# Intan_32.net
KiCad netlist of a schematic drawn in EAGLE
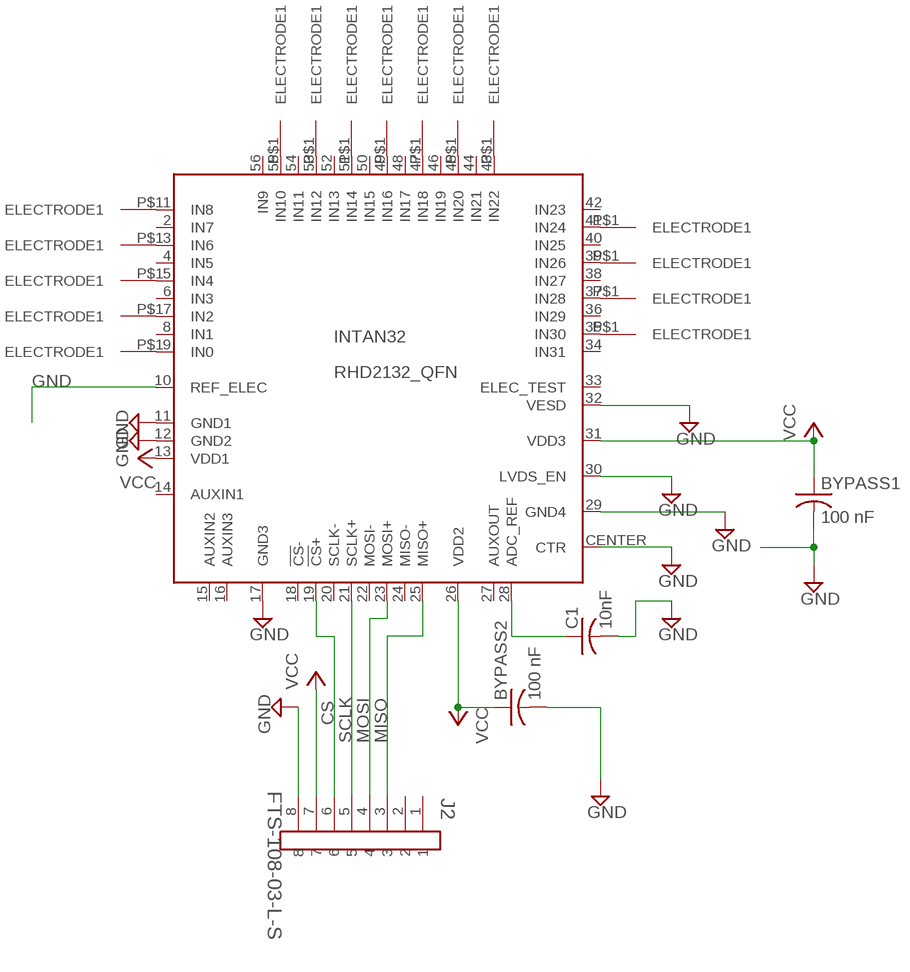
[diagram p0: schematic, sheet 1]

(export (version "E")
  (design (tool "Eeschema 10.0.6"))
  (components
    (comp (ref "BYPASS1")
      (value "100 nF")
      (footprint "eagle-import:C0402")
      (libsource (lib "eagle-import") (part "C-USC0402"))
    )
    (comp (ref "BYPASS2")
      (value "100 nF")
      (footprint "eagle-import:C0402")
      (libsource (lib "eagle-import") (part "C-USC0402"))
    )
    (comp (ref "C1")
      (value "10nF")
      (footprint "eagle-import:C0402")
      (libsource (lib "eagle-import") (part "C-USC0402"))
    )
    (comp (ref "INTAN32")
      (value "RHD2132_QFN")
      (footprint "eagle-import:QFN56_8_X_8_LARGE")
      (libsource (lib "eagle-import") (part "RHD2132_QFN"))
    )
    (comp (ref "J2")
      (value "FTS-108-03-L-S")
      (footprint "eagle-import:SAMTEC_FTS-108-03-S")
      (fields (field (name "MPN") "FTS-108-03-L-D"))
      (libsource (lib "eagle-import") (part "FTS-108-03-L-S"))
    )
    (comp (ref "U$1")
      (value "INTAN_ELECTRODE_HOLE_2323MIL")
      (footprint "eagle-import:INTAN_ELECTRODE_HOLE_23")
      (libsource (lib "eagle-import") (part "INTAN_ELECTRODE_HOLE_2323MIL"))
    )
    (comp (ref "U$2")
      (value "INTAN_ELECTRODE_HOLE_2323MIL")
      (footprint "eagle-import:INTAN_ELECTRODE_HOLE_23")
      (libsource (lib "eagle-import") (part "INTAN_ELECTRODE_HOLE_2323MIL"))
    )
    (comp (ref "U$3")
      (value "INTAN_ELECTRODE_HOLE_2323MIL")
      (footprint "eagle-import:INTAN_ELECTRODE_HOLE_23")
      (libsource (lib "eagle-import") (part "INTAN_ELECTRODE_HOLE_2323MIL"))
    )
    (comp (ref "U$4")
      (value "INTAN_ELECTRODE_HOLE_2323MIL")
      (footprint "eagle-import:INTAN_ELECTRODE_HOLE_23")
      (libsource (lib "eagle-import") (part "INTAN_ELECTRODE_HOLE_2323MIL"))
    )
    (comp (ref "U$5")
      (value "INTAN_ELECTRODE_HOLE_2323MIL")
      (footprint "eagle-import:INTAN_ELECTRODE_HOLE_23")
      (libsource (lib "eagle-import") (part "INTAN_ELECTRODE_HOLE_2323MIL"))
    )
    (comp (ref "U$6")
      (value "INTAN_ELECTRODE_HOLE_2323MIL")
      (footprint "eagle-import:INTAN_ELECTRODE_HOLE_23")
      (libsource (lib "eagle-import") (part "INTAN_ELECTRODE_HOLE_2323MIL"))
    )
    (comp (ref "U$7")
      (value "INTAN_ELECTRODE_HOLE_2323MIL")
      (footprint "eagle-import:INTAN_ELECTRODE_HOLE_23")
      (libsource (lib "eagle-import") (part "INTAN_ELECTRODE_HOLE_2323MIL"))
    )
    (comp (ref "U$8")
      (value "INTAN_ELECTRODE_HOLE_2323MIL")
      (footprint "eagle-import:INTAN_ELECTRODE_HOLE_23")
      (libsource (lib "eagle-import") (part "INTAN_ELECTRODE_HOLE_2323MIL"))
    )
    (comp (ref "U$9")
      (value "INTAN_ELECTRODE_HOLE_2323MIL")
      (footprint "eagle-import:INTAN_ELECTRODE_HOLE_23")
      (libsource (lib "eagle-import") (part "INTAN_ELECTRODE_HOLE_2323MIL"))
    )
    (comp (ref "U$10")
      (value "INTAN_ELECTRODE_HOLE_2323MIL")
      (footprint "eagle-import:INTAN_ELECTRODE_HOLE_23")
      (libsource (lib "eagle-import") (part "INTAN_ELECTRODE_HOLE_2323MIL"))
    )
    (comp (ref "U$11")
      (value "INTAN_ELECTRODE_HOLE_2323MIL")
      (footprint "eagle-import:INTAN_ELECTRODE_HOLE_23")
      (libsource (lib "eagle-import") (part "INTAN_ELECTRODE_HOLE_2323MIL"))
    )
    (comp (ref "U$12")
      (value "INTAN_ELECTRODE_HOLE_2323MIL")
      (footprint "eagle-import:INTAN_ELECTRODE_HOLE_23")
      (libsource (lib "eagle-import") (part "INTAN_ELECTRODE_HOLE_2323MIL"))
    )
    (comp (ref "U$13")
      (value "INTAN_ELECTRODE_HOLE_2323MIL")
      (footprint "eagle-import:INTAN_ELECTRODE_HOLE_23")
      (libsource (lib "eagle-import") (part "INTAN_ELECTRODE_HOLE_2323MIL"))
    )
    (comp (ref "U$14")
      (value "INTAN_ELECTRODE_HOLE_2323MIL")
      (footprint "eagle-import:INTAN_ELECTRODE_HOLE_23")
      (libsource (lib "eagle-import") (part "INTAN_ELECTRODE_HOLE_2323MIL"))
    )
    (comp (ref "U$15")
      (value "INTAN_ELECTRODE_HOLE_2323MIL")
      (footprint "eagle-import:INTAN_ELECTRODE_HOLE_23")
      (libsource (lib "eagle-import") (part "INTAN_ELECTRODE_HOLE_2323MIL"))
    )
    (comp (ref "U$16")
      (value "INTAN_ELECTRODE_HOLE_2323MIL")
      (footprint "eagle-import:INTAN_ELECTRODE_HOLE_23")
      (libsource (lib "eagle-import") (part "INTAN_ELECTRODE_HOLE_2323MIL"))
    )
  )
  (nets
    (net (code "1") (name "/CS") (class "Default")
      (node (ref "INTAN32") (pin "19") (pinfunction "~{CS}+_19") (pintype "input"))
      (node (ref "J2") (pin "6") (pinfunction "6_6") (pintype "passive"))
    )
    (net (code "2") (name "/MISO") (class "Default")
      (node (ref "INTAN32") (pin "25") (pinfunction "MISO+_25") (pintype "output"))
      (node (ref "J2") (pin "3") (pinfunction "3_3") (pintype "passive"))
    )
    (net (code "3") (name "/MOSI") (class "Default")
      (node (ref "INTAN32") (pin "23") (pinfunction "MOSI+_23") (pintype "input"))
      (node (ref "J2") (pin "4") (pinfunction "4_4") (pintype "passive"))
    )
    (net (code "4") (name "/SCLK") (class "Default")
      (node (ref "INTAN32") (pin "21") (pinfunction "SCLK+_21") (pintype "input"))
      (node (ref "J2") (pin "5") (pinfunction "5_5") (pintype "passive"))
    )
    (net (code "5") (name "GND") (class "Default")
      (node (ref "BYPASS1") (pin "2") (pinfunction "2_2") (pintype "passive"))
      (node (ref "BYPASS2") (pin "2") (pinfunction "2_2") (pintype "passive"))
      (node (ref "C1") (pin "2") (pinfunction "2_2") (pintype "passive"))
      (node (ref "INTAN32") (pin "10") (pinfunction "REF_ELEC_10") (pintype "input"))
      (node (ref "INTAN32") (pin "11") (pinfunction "GND1_11") (pintype "power_in"))
      (node (ref "INTAN32") (pin "12") (pinfunction "GND2_12") (pintype "power_in"))
      (node (ref "INTAN32") (pin "17") (pinfunction "GND3_17") (pintype "power_in"))
      (node (ref "INTAN32") (pin "29") (pinfunction "GND4_29") (pintype "power_in"))
      (node (ref "INTAN32") (pin "30") (pinfunction "LVDS_EN_30") (pintype "input"))
      (node (ref "INTAN32") (pin "32") (pinfunction "VESD_32") (pintype "power_in"))
      (node (ref "INTAN32") (pin "CENTER") (pinfunction "CTR_CENTER") (pintype "power_in"))
      (node (ref "J2") (pin "8") (pinfunction "8_8") (pintype "passive"))
    )
    (net (code "6") (name "Net-(INTAN32-ADC_REF)") (class "Default")
      (node (ref "C1") (pin "1") (pinfunction "1_1") (pintype "passive"))
      (node (ref "INTAN32") (pin "28") (pinfunction "ADC_REF_28") (pintype "passive"))
    )
    (net (code "7") (name "Net-(INTAN32-IN0)") (class "Default")
      (node (ref "INTAN32") (pin "9") (pinfunction "IN0_9") (pintype "input"))
      (node (ref "U$1") (pin "P$1") (pinfunction "ELECTRODE1_P$1") (pintype "bidirectional"))
    )
    (net (code "8") (name "Net-(INTAN32-IN2)") (class "Default")
      (node (ref "INTAN32") (pin "7") (pinfunction "IN2_7") (pintype "input"))
      (node (ref "U$2") (pin "P$1") (pinfunction "ELECTRODE1_P$1") (pintype "bidirectional"))
    )
    (net (code "9") (name "Net-(INTAN32-IN4)") (class "Default")
      (node (ref "INTAN32") (pin "5") (pinfunction "IN4_5") (pintype "input"))
      (node (ref "U$3") (pin "P$1") (pinfunction "ELECTRODE1_P$1") (pintype "bidirectional"))
    )
    (net (code "10") (name "Net-(INTAN32-IN6)") (class "Default")
      (node (ref "INTAN32") (pin "3") (pinfunction "IN6_3") (pintype "input"))
      (node (ref "U$4") (pin "P$1") (pinfunction "ELECTRODE1_P$1") (pintype "bidirectional"))
    )
    (net (code "11") (name "Net-(INTAN32-IN8)") (class "Default")
      (node (ref "INTAN32") (pin "1") (pinfunction "IN8_1") (pintype "input"))
      (node (ref "U$5") (pin "P$1") (pinfunction "ELECTRODE1_P$1") (pintype "bidirectional"))
    )
    (net (code "12") (name "Net-(INTAN32-IN10)") (class "Default")
      (node (ref "INTAN32") (pin "55") (pinfunction "IN10_55") (pintype "input"))
      (node (ref "U$6") (pin "P$1") (pinfunction "ELECTRODE1_P$1") (pintype "bidirectional"))
    )
    (net (code "13") (name "Net-(INTAN32-IN12)") (class "Default")
      (node (ref "INTAN32") (pin "53") (pinfunction "IN12_53") (pintype "input"))
      (node (ref "U$7") (pin "P$1") (pinfunction "ELECTRODE1_P$1") (pintype "bidirectional"))
    )
    (net (code "14") (name "Net-(INTAN32-IN14)") (class "Default")
      (node (ref "INTAN32") (pin "51") (pinfunction "IN14_51") (pintype "input"))
      (node (ref "U$8") (pin "P$1") (pinfunction "ELECTRODE1_P$1") (pintype "bidirectional"))
    )
    (net (code "15") (name "Net-(INTAN32-IN16)") (class "Default")
      (node (ref "INTAN32") (pin "49") (pinfunction "IN16_49") (pintype "input"))
      (node (ref "U$9") (pin "P$1") (pinfunction "ELECTRODE1_P$1") (pintype "bidirectional"))
    )
    (net (code "16") (name "Net-(INTAN32-IN18)") (class "Default")
      (node (ref "INTAN32") (pin "47") (pinfunction "IN18_47") (pintype "input"))
      (node (ref "U$10") (pin "P$1") (pinfunction "ELECTRODE1_P$1") (pintype "bidirectional"))
    )
    (net (code "17") (name "Net-(INTAN32-IN20)") (class "Default")
      (node (ref "INTAN32") (pin "45") (pinfunction "IN20_45") (pintype "input"))
      (node (ref "U$11") (pin "P$1") (pinfunction "ELECTRODE1_P$1") (pintype "bidirectional"))
    )
    (net (code "18") (name "Net-(INTAN32-IN22)") (class "Default")
      (node (ref "INTAN32") (pin "43") (pinfunction "IN22_43") (pintype "input"))
      (node (ref "U$12") (pin "P$1") (pinfunction "ELECTRODE1_P$1") (pintype "bidirectional"))
    )
    (net (code "19") (name "Net-(INTAN32-IN24)") (class "Default")
      (node (ref "INTAN32") (pin "41") (pinfunction "IN24_41") (pintype "input"))
      (node (ref "U$13") (pin "P$1") (pinfunction "ELECTRODE1_P$1") (pintype "bidirectional"))
    )
    (net (code "20") (name "Net-(INTAN32-IN26)") (class "Default")
      (node (ref "INTAN32") (pin "39") (pinfunction "IN26_39") (pintype "input"))
      (node (ref "U$14") (pin "P$1") (pinfunction "ELECTRODE1_P$1") (pintype "bidirectional"))
    )
    (net (code "21") (name "Net-(INTAN32-IN28)") (class "Default")
      (node (ref "INTAN32") (pin "37") (pinfunction "IN28_37") (pintype "input"))
      (node (ref "U$15") (pin "P$1") (pinfunction "ELECTRODE1_P$1") (pintype "bidirectional"))
    )
    (net (code "22") (name "Net-(INTAN32-IN30)") (class "Default")
      (node (ref "INTAN32") (pin "35") (pinfunction "IN30_35") (pintype "input"))
      (node (ref "U$16") (pin "P$1") (pinfunction "ELECTRODE1_P$1") (pintype "bidirectional"))
    )
    (net (code "23") (name "VCC") (class "Default")
      (node (ref "BYPASS1") (pin "1") (pinfunction "1_1") (pintype "passive"))
      (node (ref "BYPASS2") (pin "1") (pinfunction "1_1") (pintype "passive"))
      (node (ref "INTAN32") (pin "13") (pinfunction "VDD1_13") (pintype "power_in"))
      (node (ref "INTAN32") (pin "26") (pinfunction "VDD2_26") (pintype "power_in"))
      (node (ref "INTAN32") (pin "31") (pinfunction "VDD3_31") (pintype "power_in"))
      (node (ref "J2") (pin "7") (pinfunction "7_7") (pintype "passive"))
    )
    (net (code "24") (name "unconnected-(INTAN32-AUXIN1-Pad14)") (class "Default")
      (node (ref "INTAN32") (pin "14") (pinfunction "AUXIN1_14") (pintype "input"))
    )
    (net (code "25") (name "unconnected-(INTAN32-AUXIN2-Pad15)") (class "Default")
      (node (ref "INTAN32") (pin "15") (pinfunction "AUXIN2_15") (pintype "input"))
    )
    (net (code "26") (name "unconnected-(INTAN32-AUXIN3-Pad16)") (class "Default")
      (node (ref "INTAN32") (pin "16") (pinfunction "AUXIN3_16") (pintype "input"))
    )
    (net (code "27") (name "unconnected-(INTAN32-AUXOUT-Pad27)") (class "Default")
      (node (ref "INTAN32") (pin "27") (pinfunction "AUXOUT_27") (pintype "tri_state"))
    )
    (net (code "28") (name "unconnected-(INTAN32-ELEC_TEST-Pad33)") (class "Default")
      (node (ref "INTAN32") (pin "33") (pinfunction "ELEC_TEST_33") (pintype "input"))
    )
    (net (code "29") (name "unconnected-(INTAN32-IN1-Pad8)") (class "Default")
      (node (ref "INTAN32") (pin "8") (pinfunction "IN1_8") (pintype "input"))
    )
    (net (code "30") (name "unconnected-(INTAN32-IN3-Pad6)") (class "Default")
      (node (ref "INTAN32") (pin "6") (pinfunction "IN3_6") (pintype "input"))
    )
    (net (code "31") (name "unconnected-(INTAN32-IN5-Pad4)") (class "Default")
      (node (ref "INTAN32") (pin "4") (pinfunction "IN5_4") (pintype "input"))
    )
    (net (code "32") (name "unconnected-(INTAN32-IN7-Pad2)") (class "Default")
      (node (ref "INTAN32") (pin "2") (pinfunction "IN7_2") (pintype "input"))
    )
    (net (code "33") (name "unconnected-(INTAN32-IN9-Pad56)") (class "Default")
      (node (ref "INTAN32") (pin "56") (pinfunction "IN9_56") (pintype "input"))
    )
    (net (code "34") (name "unconnected-(INTAN32-IN11-Pad54)") (class "Default")
      (node (ref "INTAN32") (pin "54") (pinfunction "IN11_54") (pintype "input"))
    )
    (net (code "35") (name "unconnected-(INTAN32-IN13-Pad52)") (class "Default")
      (node (ref "INTAN32") (pin "52") (pinfunction "IN13_52") (pintype "input"))
    )
    (net (code "36") (name "unconnected-(INTAN32-IN15-Pad50)") (class "Default")
      (node (ref "INTAN32") (pin "50") (pinfunction "IN15_50") (pintype "input"))
    )
    (net (code "37") (name "unconnected-(INTAN32-IN17-Pad48)") (class "Default")
      (node (ref "INTAN32") (pin "48") (pinfunction "IN17_48") (pintype "input"))
    )
    (net (code "38") (name "unconnected-(INTAN32-IN19-Pad46)") (class "Default")
      (node (ref "INTAN32") (pin "46") (pinfunction "IN19_46") (pintype "input"))
    )
    (net (code "39") (name "unconnected-(INTAN32-IN21-Pad44)") (class "Default")
      (node (ref "INTAN32") (pin "44") (pinfunction "IN21_44") (pintype "input"))
    )
    (net (code "40") (name "unconnected-(INTAN32-IN23-Pad42)") (class "Default")
      (node (ref "INTAN32") (pin "42") (pinfunction "IN23_42") (pintype "input"))
    )
    (net (code "41") (name "unconnected-(INTAN32-IN25-Pad40)") (class "Default")
      (node (ref "INTAN32") (pin "40") (pinfunction "IN25_40") (pintype "input"))
    )
    (net (code "42") (name "unconnected-(INTAN32-IN27-Pad38)") (class "Default")
      (node (ref "INTAN32") (pin "38") (pinfunction "IN27_38") (pintype "input"))
    )
    (net (code "43") (name "unconnected-(INTAN32-IN29-Pad36)") (class "Default")
      (node (ref "INTAN32") (pin "36") (pinfunction "IN29_36") (pintype "input"))
    )
    (net (code "44") (name "unconnected-(INTAN32-IN31-Pad34)") (class "Default")
      (node (ref "INTAN32") (pin "34") (pinfunction "IN31_34") (pintype "input"))
    )
    (net (code "45") (name "unconnected-(INTAN32-MISO--Pad24)") (class "Default")
      (node (ref "INTAN32") (pin "24") (pinfunction "MISO-_24") (pintype "output"))
    )
    (net (code "46") (name "unconnected-(INTAN32-MOSI--Pad22)") (class "Default")
      (node (ref "INTAN32") (pin "22") (pinfunction "MOSI-_22") (pintype "input"))
    )
    (net (code "47") (name "unconnected-(INTAN32-SCLK--Pad20)") (class "Default")
      (node (ref "INTAN32") (pin "20") (pinfunction "SCLK-_20") (pintype "input"))
    )
    (net (code "48") (name "unconnected-(INTAN32-~{CS}--Pad18)") (class "Default")
      (node (ref "INTAN32") (pin "18") (pinfunction "~{CS}-_18") (pintype "input"))
    )
    (net (code "49") (name "unconnected-(J2-Pad1)") (class "Default")
      (node (ref "J2") (pin "1") (pinfunction "1_1") (pintype "passive"))
    )
    (net (code "50") (name "unconnected-(J2-Pad2)") (class "Default")
      (node (ref "J2") (pin "2") (pinfunction "2_2") (pintype "passive"))
    )
  )
)
